# sensor_hub.net
KiCad netlist of a schematic drawn in EAGLE
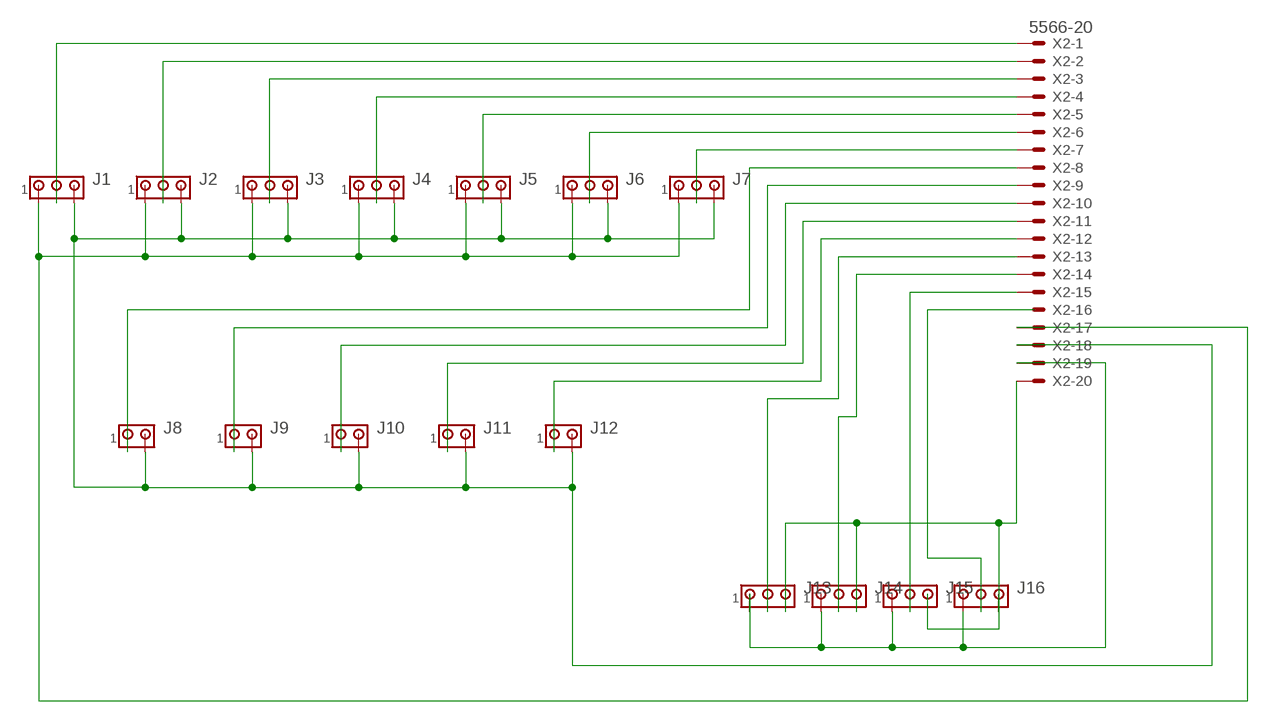
[diagram p0: schematic, sheet 1]

(export (version "E")
  (design (tool "Eeschema 10.0.6"))
  (components
    (comp (ref "J1")
      (value "MTA03-156")
      (footprint "eagle-import:1X3MTA")
      (libsource (lib "eagle-import") (part "MTA03-156"))
    )
    (comp (ref "J2")
      (value "MTA03-156")
      (footprint "eagle-import:1X3MTA")
      (libsource (lib "eagle-import") (part "MTA03-156"))
    )
    (comp (ref "J3")
      (value "MTA03-156")
      (footprint "eagle-import:1X3MTA")
      (libsource (lib "eagle-import") (part "MTA03-156"))
    )
    (comp (ref "J4")
      (value "MTA03-156")
      (footprint "eagle-import:1X3MTA")
      (libsource (lib "eagle-import") (part "MTA03-156"))
    )
    (comp (ref "J5")
      (value "MTA03-156")
      (footprint "eagle-import:1X3MTA")
      (libsource (lib "eagle-import") (part "MTA03-156"))
    )
    (comp (ref "J6")
      (value "MTA03-156")
      (footprint "eagle-import:1X3MTA")
      (libsource (lib "eagle-import") (part "MTA03-156"))
    )
    (comp (ref "J7")
      (value "MTA03-156")
      (footprint "eagle-import:1X3MTA")
      (libsource (lib "eagle-import") (part "MTA03-156"))
    )
    (comp (ref "J8")
      (value "MTA02-156")
      (footprint "eagle-import:1X2MTA")
      (libsource (lib "eagle-import") (part "MTA02-156"))
    )
    (comp (ref "J9")
      (value "MTA02-156")
      (footprint "eagle-import:1X2MTA")
      (libsource (lib "eagle-import") (part "MTA02-156"))
    )
    (comp (ref "J10")
      (value "MTA02-156")
      (footprint "eagle-import:1X2MTA")
      (libsource (lib "eagle-import") (part "MTA02-156"))
    )
    (comp (ref "J11")
      (value "MTA02-156")
      (footprint "eagle-import:1X2MTA")
      (libsource (lib "eagle-import") (part "MTA02-156"))
    )
    (comp (ref "J12")
      (value "MTA02-156")
      (footprint "eagle-import:1X2MTA")
      (libsource (lib "eagle-import") (part "MTA02-156"))
    )
    (comp (ref "J13")
      (value "MTA03-156")
      (footprint "eagle-import:1X3MTA")
      (libsource (lib "eagle-import") (part "MTA03-156"))
    )
    (comp (ref "J14")
      (value "MTA03-156")
      (footprint "eagle-import:1X3MTA")
      (libsource (lib "eagle-import") (part "MTA03-156"))
    )
    (comp (ref "J15")
      (value "MTA03-156")
      (footprint "eagle-import:1X3MTA")
      (libsource (lib "eagle-import") (part "MTA03-156"))
    )
    (comp (ref "J16")
      (value "MTA03-156")
      (footprint "eagle-import:1X3MTA")
      (libsource (lib "eagle-import") (part "MTA03-156"))
    )
    (comp (ref "X2")
      (value "5566-20")
      (footprint "eagle-import:5566-20")
      (libsource (lib "eagle-import") (part "5566-20"))
    )
  )
  (nets
    (net (code "1") (name "Net-(X2A-S)") (class "Default")
      (node (ref "J1") (pin "2") (pinfunction "2_2") (pintype "passive"))
      (node (ref "X2") (pin "1") (pinfunction "S_1") (pintype "passive"))
    )
    (net (code "2") (name "Net-(X2B-S)") (class "Default")
      (node (ref "J10") (pin "1") (pinfunction "1_1") (pintype "passive"))
      (node (ref "X2") (pin "10") (pinfunction "S_10") (pintype "passive"))
    )
    (net (code "3") (name "Net-(X2C-S)") (class "Default")
      (node (ref "J11") (pin "1") (pinfunction "1_1") (pintype "passive"))
      (node (ref "X2") (pin "11") (pinfunction "S_11") (pintype "passive"))
    )
    (net (code "4") (name "Net-(X2D-S)") (class "Default")
      (node (ref "J12") (pin "1") (pinfunction "1_1") (pintype "passive"))
      (node (ref "X2") (pin "12") (pinfunction "S_12") (pintype "passive"))
    )
    (net (code "5") (name "Net-(X2E-S)") (class "Default")
      (node (ref "J13") (pin "2") (pinfunction "2_2") (pintype "passive"))
      (node (ref "X2") (pin "13") (pinfunction "S_13") (pintype "passive"))
    )
    (net (code "6") (name "Net-(X2F-S)") (class "Default")
      (node (ref "J14") (pin "2") (pinfunction "2_2") (pintype "passive"))
      (node (ref "X2") (pin "14") (pinfunction "S_14") (pintype "passive"))
    )
    (net (code "7") (name "Net-(X2G-S)") (class "Default")
      (node (ref "J15") (pin "2") (pinfunction "2_2") (pintype "passive"))
      (node (ref "X2") (pin "15") (pinfunction "S_15") (pintype "passive"))
    )
    (net (code "8") (name "Net-(X2I-S)") (class "Default")
      (node (ref "J1") (pin "1") (pinfunction "1_1") (pintype "passive"))
      (node (ref "J2") (pin "1") (pinfunction "1_1") (pintype "passive"))
      (node (ref "J3") (pin "1") (pinfunction "1_1") (pintype "passive"))
      (node (ref "J4") (pin "1") (pinfunction "1_1") (pintype "passive"))
      (node (ref "J5") (pin "1") (pinfunction "1_1") (pintype "passive"))
      (node (ref "J6") (pin "1") (pinfunction "1_1") (pintype "passive"))
      (node (ref "J7") (pin "1") (pinfunction "1_1") (pintype "passive"))
      (node (ref "X2") (pin "17") (pinfunction "S_17") (pintype "passive"))
    )
    (net (code "9") (name "Net-(X2J-S)") (class "Default")
      (node (ref "J1") (pin "3") (pinfunction "3_3") (pintype "passive"))
      (node (ref "J10") (pin "2") (pinfunction "2_2") (pintype "passive"))
      (node (ref "J11") (pin "2") (pinfunction "2_2") (pintype "passive"))
      (node (ref "J12") (pin "2") (pinfunction "2_2") (pintype "passive"))
      (node (ref "J2") (pin "3") (pinfunction "3_3") (pintype "passive"))
      (node (ref "J3") (pin "3") (pinfunction "3_3") (pintype "passive"))
      (node (ref "J4") (pin "3") (pinfunction "3_3") (pintype "passive"))
      (node (ref "J5") (pin "3") (pinfunction "3_3") (pintype "passive"))
      (node (ref "J6") (pin "3") (pinfunction "3_3") (pintype "passive"))
      (node (ref "J7") (pin "3") (pinfunction "3_3") (pintype "passive"))
      (node (ref "J8") (pin "2") (pinfunction "2_2") (pintype "passive"))
      (node (ref "J9") (pin "2") (pinfunction "2_2") (pintype "passive"))
      (node (ref "X2") (pin "18") (pinfunction "S_18") (pintype "passive"))
    )
    (net (code "10") (name "Net-(X2K-S)") (class "Default")
      (node (ref "J14") (pin "1") (pinfunction "1_1") (pintype "passive"))
      (node (ref "J15") (pin "1") (pinfunction "1_1") (pintype "passive"))
      (node (ref "J16") (pin "1") (pinfunction "1_1") (pintype "passive"))
      (node (ref "X2") (pin "19") (pinfunction "S_19") (pintype "passive"))
    )
    (net (code "11") (name "Net-(X2L-S)") (class "Default")
      (node (ref "J2") (pin "2") (pinfunction "2_2") (pintype "passive"))
      (node (ref "X2") (pin "2") (pinfunction "S_2") (pintype "passive"))
    )
    (net (code "12") (name "Net-(X2M-S)") (class "Default")
      (node (ref "J13") (pin "3") (pinfunction "3_3") (pintype "passive"))
      (node (ref "J14") (pin "3") (pinfunction "3_3") (pintype "passive"))
      (node (ref "J16") (pin "3") (pinfunction "3_3") (pintype "passive"))
      (node (ref "X2") (pin "20") (pinfunction "S_20") (pintype "passive"))
    )
    (net (code "13") (name "Net-(X2N-S)") (class "Default")
      (node (ref "J3") (pin "2") (pinfunction "2_2") (pintype "passive"))
      (node (ref "X2") (pin "3") (pinfunction "S_3") (pintype "passive"))
    )
    (net (code "14") (name "Net-(X2O-S)") (class "Default")
      (node (ref "J4") (pin "2") (pinfunction "2_2") (pintype "passive"))
      (node (ref "X2") (pin "4") (pinfunction "S_4") (pintype "passive"))
    )
    (net (code "15") (name "Net-(X2P-S)") (class "Default")
      (node (ref "J5") (pin "2") (pinfunction "2_2") (pintype "passive"))
      (node (ref "X2") (pin "5") (pinfunction "S_5") (pintype "passive"))
    )
    (net (code "16") (name "Net-(X2Q-S)") (class "Default")
      (node (ref "J6") (pin "2") (pinfunction "2_2") (pintype "passive"))
      (node (ref "X2") (pin "6") (pinfunction "S_6") (pintype "passive"))
    )
    (net (code "17") (name "Net-(X2R-S)") (class "Default")
      (node (ref "J7") (pin "2") (pinfunction "2_2") (pintype "passive"))
      (node (ref "X2") (pin "7") (pinfunction "S_7") (pintype "passive"))
    )
    (net (code "18") (name "Net-(X2S-S)") (class "Default")
      (node (ref "J8") (pin "1") (pinfunction "1_1") (pintype "passive"))
      (node (ref "X2") (pin "8") (pinfunction "S_8") (pintype "passive"))
    )
    (net (code "19") (name "Net-(X2T-S)") (class "Default")
      (node (ref "J9") (pin "1") (pinfunction "1_1") (pintype "passive"))
      (node (ref "X2") (pin "9") (pinfunction "S_9") (pintype "passive"))
    )
    (net (code "20") (name "unconnected-(J13-Pad1)") (class "Default")
      (node (ref "J13") (pin "1") (pinfunction "1_1") (pintype "passive"))
    )
    (net (code "21") (name "unconnected-(J15-Pad3)") (class "Default")
      (node (ref "J15") (pin "3") (pinfunction "3_3") (pintype "passive"))
    )
    (net (code "22") (name "unconnected-(J16-Pad2)") (class "Default")
      (node (ref "J16") (pin "2") (pinfunction "2_2") (pintype "passive"))
    )
    (net (code "23") (name "unconnected-(X2H-S-Pad16)") (class "Default")
      (node (ref "X2") (pin "16") (pinfunction "S_16") (pintype "passive"))
    )
  )
)
